# MP3438_Prototype.net
KiCad netlist of a schematic drawn in Altium Designer
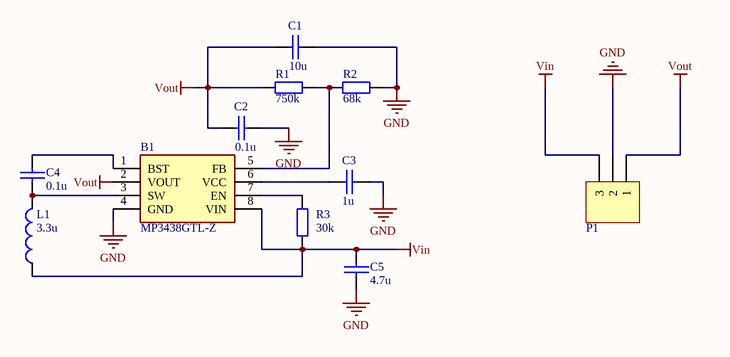
[diagram p0: MP3438 Prototype.SchDoc]

(export (version "E")
  (design (tool "Eeschema 10.0.6"))
  (components
    (comp (ref "B1")
      (value "MP3438GTL-Z")
      (footprint "SOTFL50P160X60-8N")
      (description "Switching Voltage Regulators 2A, 16V, High Efficiency Fully-Integrated Synchronous Boost Converter")
      (fields (field (name "MOUSER PART NUMBER") "946-MP3438GTL-Z"))
      (libsource (lib "ece components") (part "MP3438GTL-Z"))
    )
    (comp (ref "C1")
      (value "10u")
      (footprint "ece-CC2012-0805")
      (description "SM capacitor")
      (libsource (lib "ece components") (part "CAP SM0805"))
    )
    (comp (ref "C2")
      (value "0.1u")
      (footprint "ece-CC2012-0805")
      (description "SM capacitor")
      (libsource (lib "ece components") (part "CAP SM0805"))
    )
    (comp (ref "C3")
      (value "1u")
      (footprint "ece-CC2012-0805")
      (description "SM capacitor")
      (libsource (lib "ece components") (part "CAP SM0805"))
    )
    (comp (ref "C4")
      (value "0.1u")
      (footprint "ece-CC2012-0805")
      (description "SM capacitor")
      (libsource (lib "ece components") (part "CAP SM0805"))
    )
    (comp (ref "C5")
      (value "4.7u")
      (footprint "ece-CC2012-0805")
      (description "SM capacitor")
      (libsource (lib "ece components") (part "CAP SM0805"))
    )
    (comp (ref "L1")
      (value "3.3u")
      (footprint "MPL-AL4020")
      (description "Low-Resistance Molded Inductor 3.3µH")
      (libsource (lib "ece components") (part "MPL-AL4020-3R3"))
    )
    (comp (ref "P1")
      (value "Header 3")
      (footprint "ece-HDR1X3")
      (description "Header, 3-Pin")
      (fields (field (name "PUBLISHER") "Altium Limited"))
      (libsource (lib "ece components") (part "Header 3"))
    )
    (comp (ref "R1")
      (value "750k")
      (footprint "RESC2012-0805SM")
      (description "SM resistor")
      (libsource (lib "") (part "Res SM 0805_1"))
    )
    (comp (ref "R2")
      (value "68k")
      (footprint "RESC2012-0805SM")
      (description "SM resistor")
      (libsource (lib "") (part "Res SM 0805_2"))
    )
    (comp (ref "R3")
      (value "30k")
      (footprint "RESC2012-0805SM")
      (description "SM resistor")
      (libsource (lib "ece components") (part "Res SM 0805"))
    )
  )
  (nets
    (net (code "1") (name "GND") (class "Default")
      (node (ref "B1") (pin "4") (pinfunction "GND_4") (pintype "passive"))
      (node (ref "C1") (pin "1") (pinfunction "1_1") (pintype "passive"))
      (node (ref "C2") (pin "1") (pinfunction "1_1") (pintype "passive"))
      (node (ref "C3") (pin "1") (pinfunction "1_1") (pintype "passive"))
      (node (ref "C5") (pin "2") (pinfunction "2_2") (pintype "passive"))
      (node (ref "P1") (pin "2") (pinfunction "2_2") (pintype "passive"))
      (node (ref "R2") (pin "1") (pinfunction "1_1") (pintype "passive"))
    )
    (net (code "2") (name "Net-(B1-BST)") (class "Default")
      (node (ref "B1") (pin "1") (pinfunction "BST_1") (pintype "passive"))
      (node (ref "C4") (pin "1") (pinfunction "1_1") (pintype "passive"))
    )
    (net (code "3") (name "Net-(B1-EN)") (class "Default")
      (node (ref "B1") (pin "7") (pinfunction "EN_7") (pintype "passive"))
      (node (ref "R3") (pin "2") (pinfunction "2_2") (pintype "passive"))
    )
    (net (code "4") (name "Net-(B1-FB)") (class "Default")
      (node (ref "B1") (pin "5") (pinfunction "FB_5") (pintype "passive"))
      (node (ref "R1") (pin "2") (pinfunction "2_2") (pintype "passive"))
      (node (ref "R2") (pin "2") (pinfunction "2_2") (pintype "passive"))
    )
    (net (code "5") (name "Net-(B1-SW)") (class "Default")
      (node (ref "B1") (pin "3") (pinfunction "SW_3") (pintype "passive"))
      (node (ref "C4") (pin "2") (pinfunction "2_2") (pintype "passive"))
      (node (ref "L1") (pin "2") (pinfunction "2_2") (pintype "passive"))
    )
    (net (code "6") (name "Net-(B1-VCC)") (class "Default")
      (node (ref "B1") (pin "6") (pinfunction "VCC_6") (pintype "passive"))
      (node (ref "C3") (pin "2") (pinfunction "2_2") (pintype "passive"))
    )
    (net (code "7") (name "Vin") (class "Default")
      (node (ref "B1") (pin "8") (pinfunction "VIN_8") (pintype "passive"))
      (node (ref "C5") (pin "1") (pinfunction "1_1") (pintype "passive"))
      (node (ref "L1") (pin "1") (pinfunction "1_1") (pintype "passive"))
      (node (ref "P1") (pin "3") (pinfunction "3_3") (pintype "passive"))
      (node (ref "R3") (pin "1") (pinfunction "1_1") (pintype "passive"))
    )
    (net (code "8") (name "Vout") (class "Default")
      (node (ref "B1") (pin "2") (pinfunction "VOUT_2") (pintype "passive"))
      (node (ref "C1") (pin "2") (pinfunction "2_2") (pintype "passive"))
      (node (ref "C2") (pin "2") (pinfunction "2_2") (pintype "passive"))
      (node (ref "P1") (pin "1") (pinfunction "1_1") (pintype "passive"))
      (node (ref "R1") (pin "1") (pinfunction "1_1") (pintype "passive"))
    )
  )
)
